# TokTok_Bluetooth.net
KiCad netlist of a schematic drawn in EAGLE
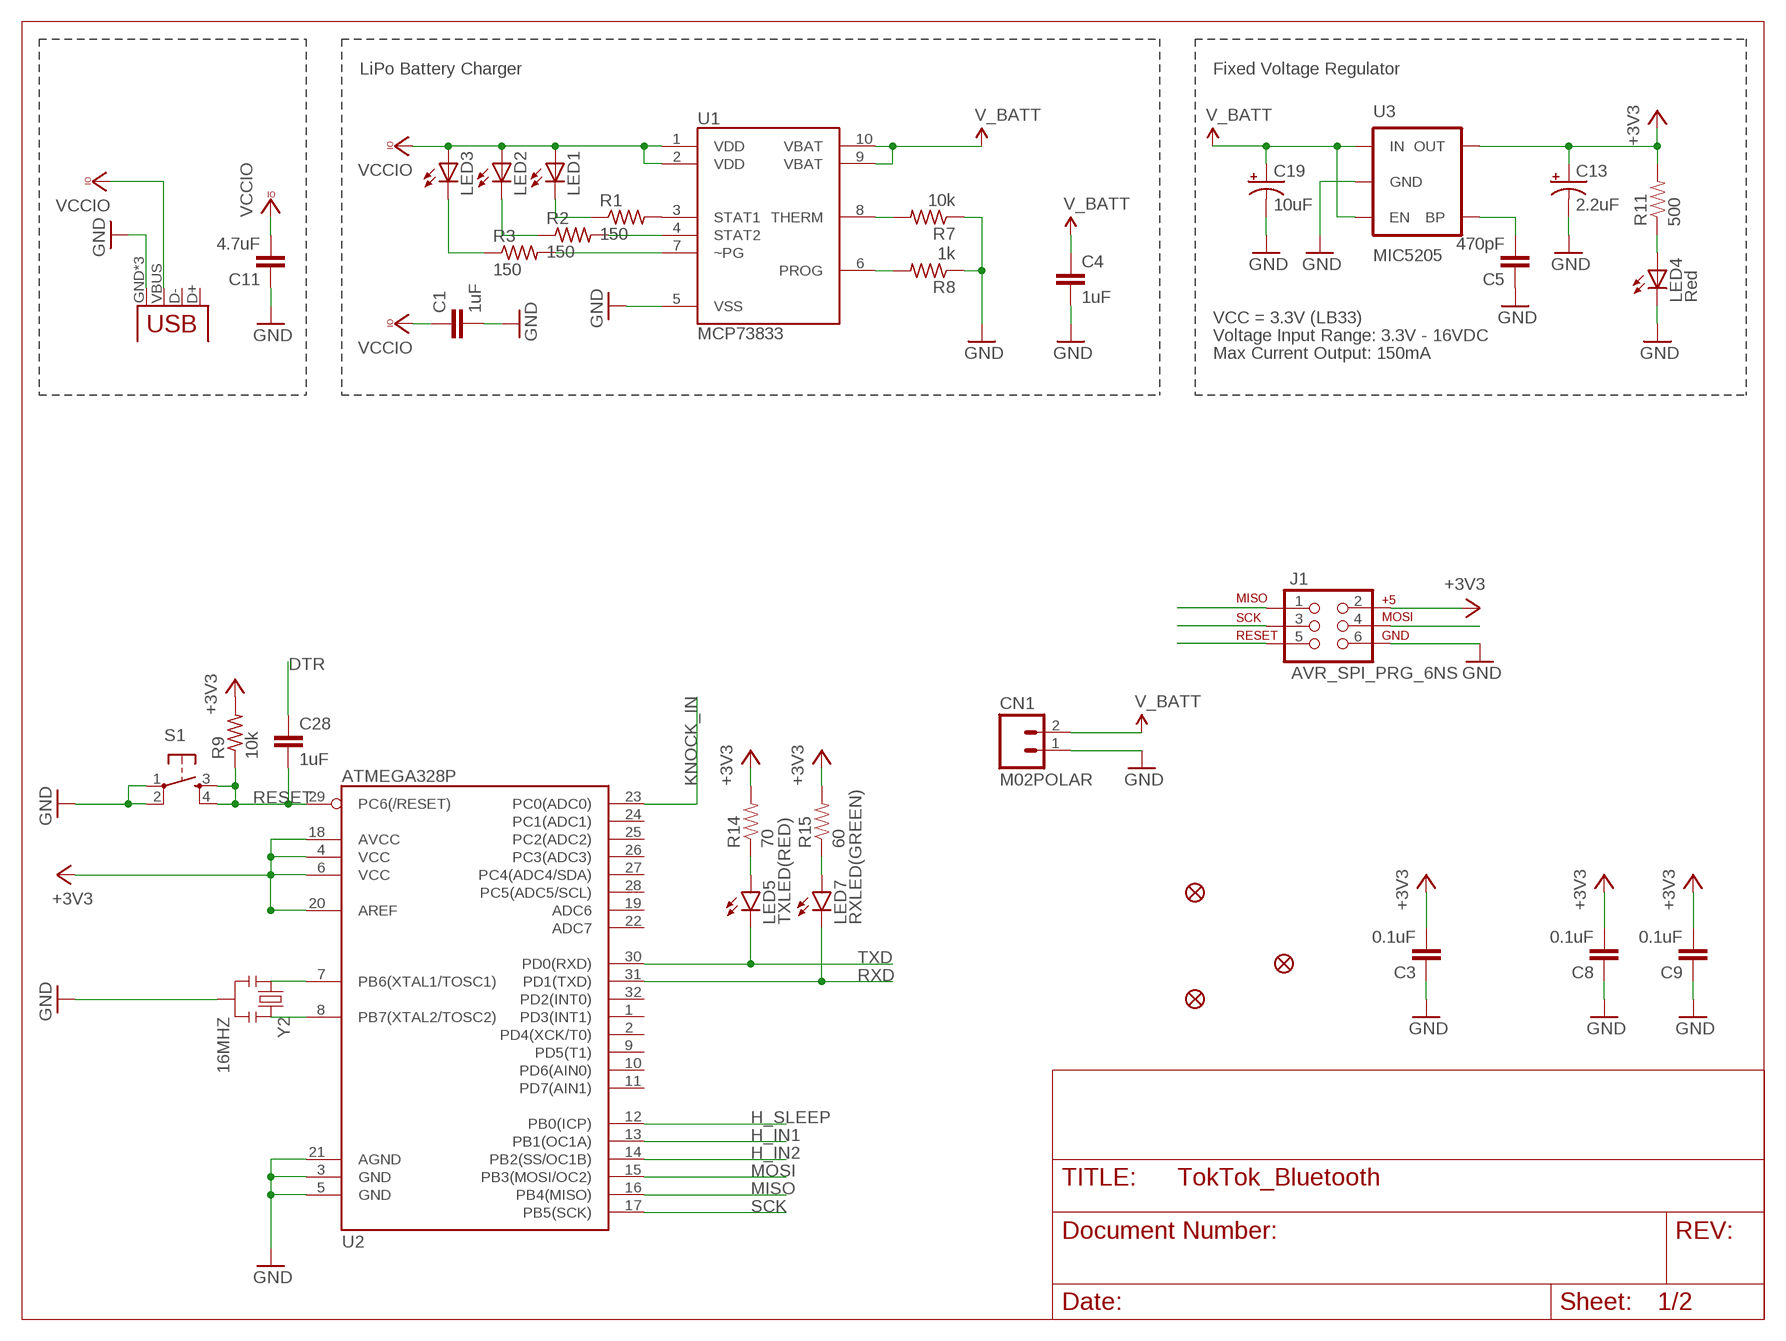
[diagram p0: schematic, sheet 1, part 1 of 2]
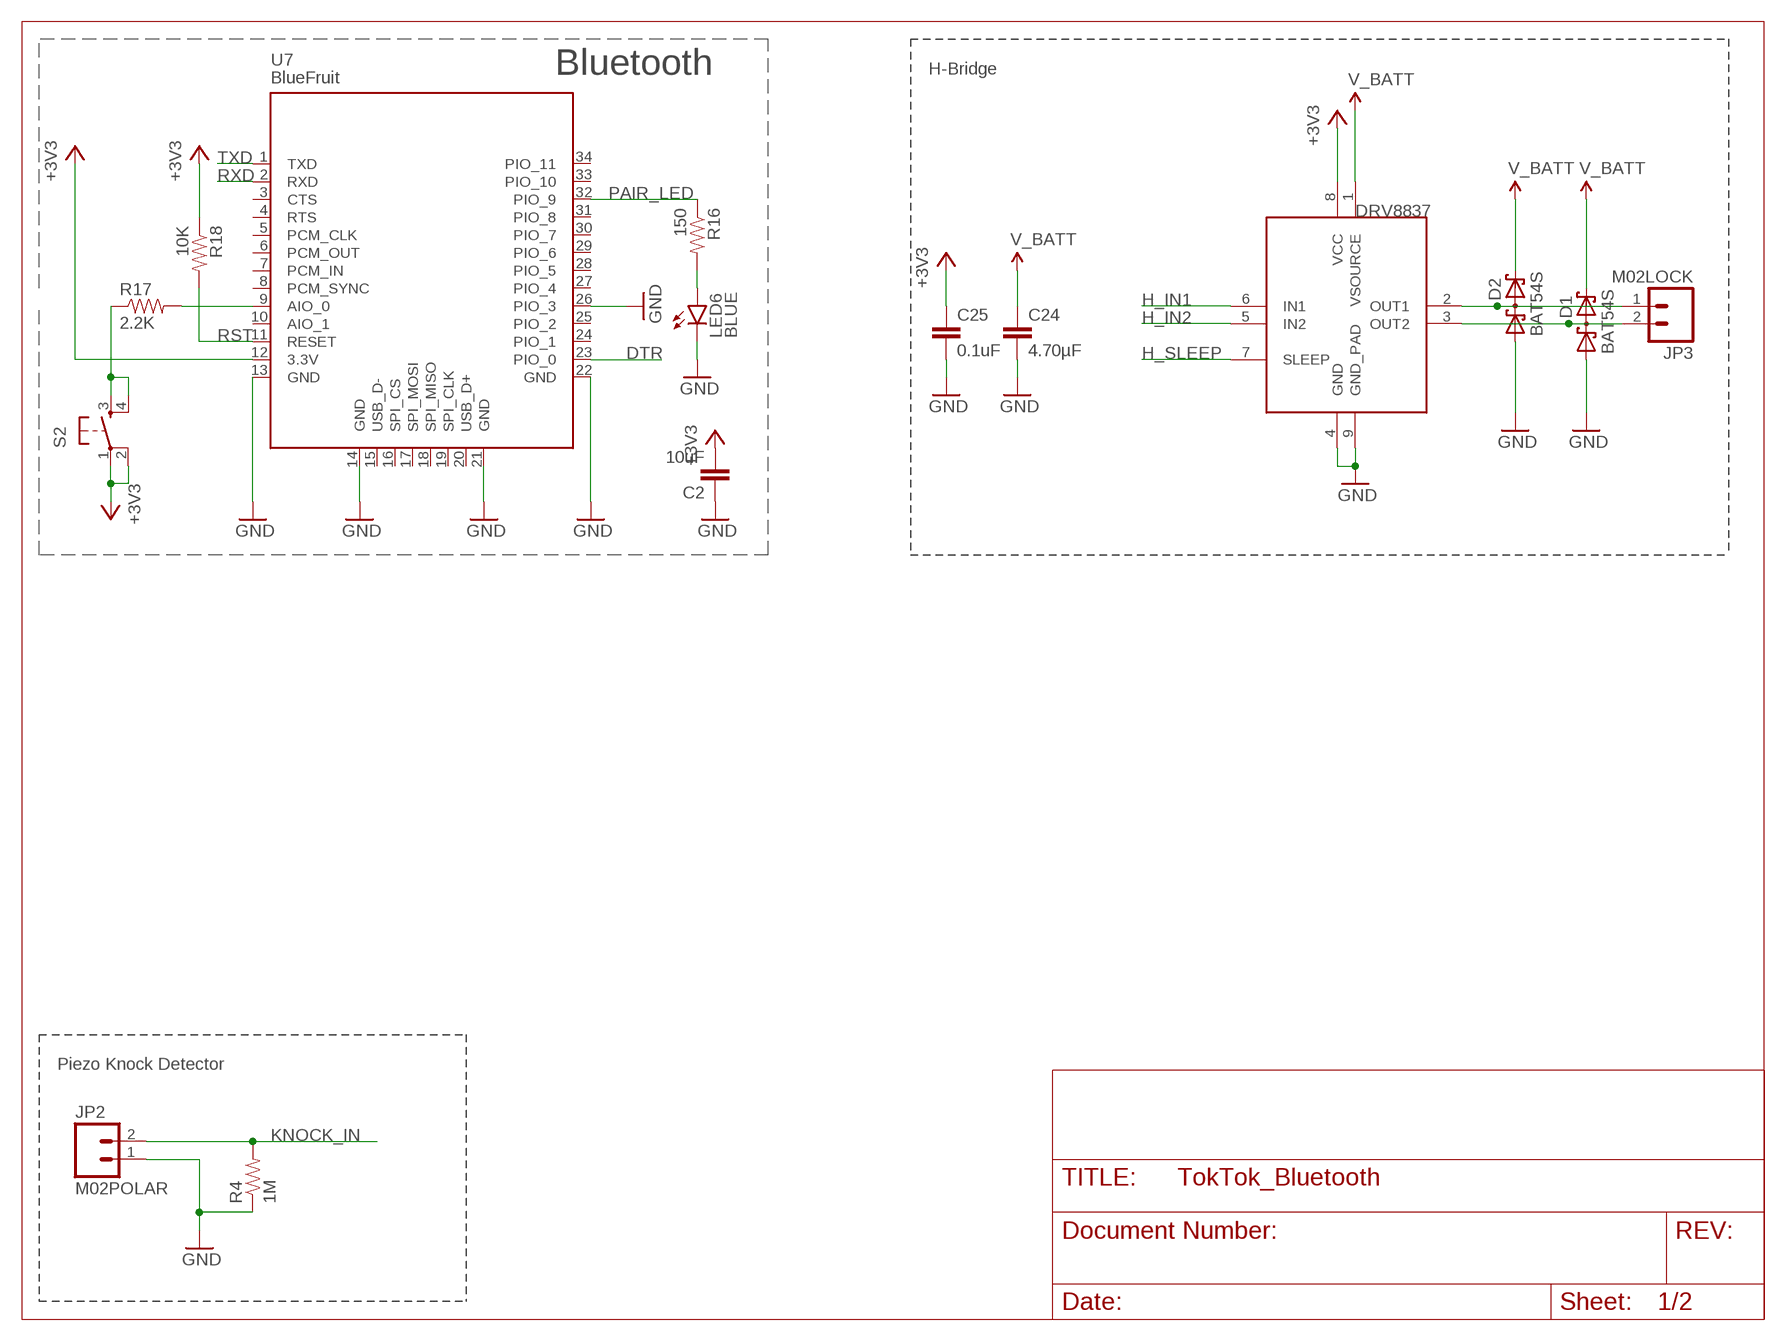
[diagram p1: schematic, sheet 1, part 2 of 2]

(export (version "E")
  (design (tool "Eeschema 10.0.6"))
  (components
    (comp (ref "C1")
      (value "1uF")
      (footprint "eagle-import:C0805K")
      (libsource (lib "eagle-import") (part "C-EUC0805K"))
    )
    (comp (ref "C2")
      (value "10uF")
      (footprint "eagle-import:0805")
      (libsource (lib "eagle-import") (part "CAP0805"))
    )
    (comp (ref "C3")
      (value "0.1uF")
      (footprint "eagle-import:C0805K")
      (libsource (lib "eagle-import") (part "C-EUC0805K"))
    )
    (comp (ref "C4")
      (value "1uF")
      (footprint "eagle-import:C0805K")
      (libsource (lib "eagle-import") (part "C-EUC0805K"))
    )
    (comp (ref "C5")
      (value "470pF")
      (footprint "eagle-import:0805")
      (libsource (lib "eagle-import") (part "CAP0805"))
    )
    (comp (ref "C8")
      (value "0.1uF")
      (footprint "eagle-import:C0805K")
      (libsource (lib "eagle-import") (part "C-EUC0805K"))
    )
    (comp (ref "C9")
      (value "0.1uF")
      (footprint "eagle-import:C0805K")
      (libsource (lib "eagle-import") (part "C-EUC0805K"))
    )
    (comp (ref "C11")
      (value "4.7uF")
      (footprint "eagle-import:C0805K")
      (libsource (lib "eagle-import") (part "C-EUC0805K"))
    )
    (comp (ref "C13")
      (value "2.2uF")
      (footprint "eagle-import:EIA3216")
      (libsource (lib "eagle-import") (part "CAP_POL1206"))
    )
    (comp (ref "C19")
      (value "10uF")
      (footprint "eagle-import:EIA3216")
      (libsource (lib "eagle-import") (part "CAP_POL1206"))
    )
    (comp (ref "C24")
      (value "4.70µF")
      (footprint "eagle-import:0805")
      (libsource (lib "eagle-import") (part "CAP0805"))
    )
    (comp (ref "C25")
      (value "0.1uF")
      (footprint "eagle-import:0805")
      (libsource (lib "eagle-import") (part "CAP0805"))
    )
    (comp (ref "C28")
      (value "1uF")
      (footprint "eagle-import:0805")
      (libsource (lib "eagle-import") (part "CAP0805"))
    )
    (comp (ref "CN1")
      (value "M02POLAR")
      (footprint "eagle-import:MOLEX-1X2")
      (libsource (lib "eagle-import") (part "M02POLAR"))
    )
    (comp (ref "D1")
      (value "BAT54S")
      (footprint "eagle-import:SOT23")
      (libsource (lib "eagle-import") (part "BAT54S"))
    )
    (comp (ref "D2")
      (value "BAT54S")
      (footprint "eagle-import:SOT23")
      (libsource (lib "eagle-import") (part "BAT54S"))
    )
    (comp (ref "FID1")
      (value "FIDUCIAL\"\"")
      (footprint "eagle-import:FIDUCIAL_1MM")
      (libsource (lib "eagle-import") (part "FIDUCIAL{dblquote}{dblquote}"))
    )
    (comp (ref "FID2")
      (value "FIDUCIAL\"\"")
      (footprint "eagle-import:FIDUCIAL_1MM")
      (libsource (lib "eagle-import") (part "FIDUCIAL{dblquote}{dblquote}"))
    )
    (comp (ref "FID3")
      (value "FIDUCIAL\"\"")
      (footprint "eagle-import:FIDUCIAL_1MM")
      (libsource (lib "eagle-import") (part "FIDUCIAL{dblquote}{dblquote}"))
    )
    (comp (ref "IC2")
      (value "DRV8837")
      (footprint "eagle-import:WSON-8")
      (libsource (lib "eagle-import") (part "DRV8837"))
    )
    (comp (ref "J1")
      (value "AVR_SPI_PRG_6NS")
      (footprint "eagle-import:2X3-NS")
      (libsource (lib "eagle-import") (part "AVR_SPI_PRG_6NS"))
    )
    (comp (ref "JP1")
      (value "USB-MICROB")
      (footprint "eagle-import:USB-MICROB")
      (libsource (lib "eagle-import") (part "USB-MICROB"))
    )
    (comp (ref "JP2")
      (value "M02POLAR")
      (footprint "eagle-import:MOLEX-1X2")
      (libsource (lib "eagle-import") (part "M02POLAR"))
    )
    (comp (ref "JP3")
      (value "M02LOCK")
      (footprint "eagle-import:1X02_LOCK")
      (libsource (lib "eagle-import") (part "M02LOCK"))
    )
    (comp (ref "LED1")
      (value "LEDCHIPLED_1206")
      (footprint "eagle-import:CHIPLED_1206")
      (libsource (lib "eagle-import") (part "LEDCHIPLED_1206"))
    )
    (comp (ref "LED2")
      (value "LEDCHIPLED_1206")
      (footprint "eagle-import:CHIPLED_1206")
      (libsource (lib "eagle-import") (part "LEDCHIPLED_1206"))
    )
    (comp (ref "LED3")
      (value "LEDCHIPLED_1206")
      (footprint "eagle-import:CHIPLED_1206")
      (libsource (lib "eagle-import") (part "LEDCHIPLED_1206"))
    )
    (comp (ref "LED4")
      (value "Red")
      (footprint "eagle-import:LED-1206")
      (libsource (lib "eagle-import") (part "LED-RED1206"))
    )
    (comp (ref "LED5")
      (value "TXLED(RED)")
      (footprint "eagle-import:LED-1206")
      (libsource (lib "eagle-import") (part "LED1206"))
    )
    (comp (ref "LED6")
      (value "BLUE")
      (footprint "eagle-import:LED-1206")
      (libsource (lib "eagle-import") (part "LED1206"))
    )
    (comp (ref "LED7")
      (value "RXLED(GREEN)")
      (footprint "eagle-import:LED-1206")
      (libsource (lib "eagle-import") (part "LED1206"))
    )
    (comp (ref "R1")
      (value "150")
      (footprint "eagle-import:M0805")
      (libsource (lib "eagle-import") (part "R-US_M0805"))
    )
    (comp (ref "R2")
      (value "150")
      (footprint "eagle-import:M0805")
      (libsource (lib "eagle-import") (part "R-US_M0805"))
    )
    (comp (ref "R3")
      (value "150")
      (footprint "eagle-import:M0805")
      (libsource (lib "eagle-import") (part "R-US_M0805"))
    )
    (comp (ref "R4")
      (value "1M")
      (footprint "eagle-import:0805")
      (libsource (lib "eagle-import") (part "RESISTOR0805-RES"))
    )
    (comp (ref "R7")
      (value "10k")
      (footprint "eagle-import:M0805")
      (libsource (lib "eagle-import") (part "R-US_M0805"))
    )
    (comp (ref "R8")
      (value "1k")
      (footprint "eagle-import:M0805")
      (libsource (lib "eagle-import") (part "R-US_M0805"))
    )
    (comp (ref "R9")
      (value "10k")
      (footprint "eagle-import:M0805")
      (libsource (lib "eagle-import") (part "R-US_M0805"))
    )
    (comp (ref "R11")
      (value "500")
      (footprint "eagle-import:0805")
      (libsource (lib "eagle-import") (part "RESISTOR0805-RES"))
    )
    (comp (ref "R14")
      (value "70")
      (footprint "eagle-import:0805")
      (libsource (lib "eagle-import") (part "RESISTOR0805-RES"))
    )
    (comp (ref "R15")
      (value "60")
      (footprint "eagle-import:0805")
      (libsource (lib "eagle-import") (part "RESISTOR0805-RES"))
    )
    (comp (ref "R16")
      (value "150")
      (footprint "eagle-import:0805")
      (libsource (lib "eagle-import") (part "RESISTOR0805-RES"))
    )
    (comp (ref "R17")
      (value "2.2K")
      (footprint "eagle-import:0805")
      (libsource (lib "eagle-import") (part "RESISTOR0805-RES"))
    )
    (comp (ref "R18")
      (value "10K")
      (footprint "eagle-import:0805")
      (libsource (lib "eagle-import") (part "RESISTOR0805-RES"))
    )
    (comp (ref "S1")
      (value "TAC_SWITCHSMD")
      (footprint "eagle-import:TACTILE-SWITCH-SMD")
      (libsource (lib "eagle-import") (part "TAC_SWITCHSMD"))
    )
    (comp (ref "S2")
      (value "TAC_SWITCHSMD")
      (footprint "eagle-import:TACTILE-SWITCH-SMD")
      (libsource (lib "eagle-import") (part "TAC_SWITCHSMD"))
    )
    (comp (ref "U1")
      (value "MCP73833")
      (footprint "eagle-import:MSOP-10")
      (libsource (lib "eagle-import") (part "MCP73833"))
    )
    (comp (ref "U2")
      (value "ATMEGA328P")
      (footprint "eagle-import:TQFP32-08")
      (libsource (lib "eagle-import") (part "ATMEGA328_SMT"))
    )
    (comp (ref "U3")
      (value "MIC5205")
      (footprint "eagle-import:SOT23-5")
      (libsource (lib "eagle-import") (part "V_REG_LDOSMD"))
    )
    (comp (ref "U7")
      (value "BlueFruit")
      (footprint "eagle-import:BLUETOOTH_MODULE")
      (libsource (lib "eagle-import") (part "BLUETOOTH_MODULE"))
    )
    (comp (ref "Y2")
      (value "16MHZ")
      (footprint "eagle-import:RESONATOR-SMD")
      (libsource (lib "eagle-import") (part "RESONATOR8MHZ"))
    )
  )
  (nets
    (net (code "1") (name "+3V3") (class "Default")
      (node (ref "C13") (pin "A") (pinfunction "+_A") (pintype "passive"))
      (node (ref "C2") (pin "2") (pinfunction "2_2") (pintype "passive"))
      (node (ref "C25") (pin "1") (pinfunction "1_1") (pintype "passive"))
      (node (ref "C3") (pin "2") (pinfunction "2_2") (pintype "passive"))
      (node (ref "C8") (pin "2") (pinfunction "2_2") (pintype "passive"))
      (node (ref "C9") (pin "2") (pinfunction "2_2") (pintype "passive"))
      (node (ref "IC2") (pin "8") (pinfunction "VCC_8") (pintype "bidirectional"))
      (node (ref "J1") (pin "2") (pinfunction "2_2") (pintype "passive"))
      (node (ref "R11") (pin "2") (pinfunction "2_2") (pintype "passive"))
      (node (ref "R14") (pin "2") (pinfunction "2_2") (pintype "passive"))
      (node (ref "R15") (pin "2") (pinfunction "2_2") (pintype "passive"))
      (node (ref "R18") (pin "1") (pinfunction "1_1") (pintype "passive"))
      (node (ref "R9") (pin "2") (pinfunction "2_2") (pintype "passive"))
      (node (ref "S2") (pin "1") (pinfunction "1_1") (pintype "passive"))
      (node (ref "S2") (pin "2") (pinfunction "2_2") (pintype "passive"))
      (node (ref "U2") (pin "18") (pinfunction "AVCC_18") (pintype "bidirectional"))
      (node (ref "U2") (pin "20") (pinfunction "AREF_20") (pintype "bidirectional"))
      (node (ref "U2") (pin "4") (pinfunction "VCC_4") (pintype "bidirectional"))
      (node (ref "U2") (pin "6") (pinfunction "VCC_6") (pintype "bidirectional"))
      (node (ref "U3") (pin "5") (pinfunction "OUT_5") (pintype "passive"))
      (node (ref "U7") (pin "12") (pinfunction "3.3V_12") (pintype "power_in"))
    )
    (net (code "2") (name "DTR") (class "Default")
      (node (ref "C28") (pin "1") (pinfunction "1_1") (pintype "passive"))
      (node (ref "U7") (pin "23") (pinfunction "PIO_0_23") (pintype "bidirectional"))
    )
    (net (code "3") (name "GND") (class "Default")
      (node (ref "C1") (pin "2") (pinfunction "2_2") (pintype "passive"))
      (node (ref "C11") (pin "1") (pinfunction "1_1") (pintype "passive"))
      (node (ref "C13") (pin "C") (pinfunction "-_C") (pintype "passive"))
      (node (ref "C19") (pin "C") (pinfunction "-_C") (pintype "passive"))
      (node (ref "C2") (pin "1") (pinfunction "1_1") (pintype "passive"))
      (node (ref "C24") (pin "2") (pinfunction "2_2") (pintype "passive"))
      (node (ref "C25") (pin "2") (pinfunction "2_2") (pintype "passive"))
      (node (ref "C3") (pin "1") (pinfunction "1_1") (pintype "passive"))
      (node (ref "C4") (pin "2") (pinfunction "2_2") (pintype "passive"))
      (node (ref "C5") (pin "1") (pinfunction "1_1") (pintype "passive"))
      (node (ref "C8") (pin "1") (pinfunction "1_1") (pintype "passive"))
      (node (ref "C9") (pin "1") (pinfunction "1_1") (pintype "passive"))
      (node (ref "CN1") (pin "1") (pinfunction "1_1") (pintype "passive"))
      (node (ref "D1") (pin "1") (pinfunction "A1_1") (pintype "passive"))
      (node (ref "D2") (pin "1") (pinfunction "A1_1") (pintype "passive"))
      (node (ref "IC2") (pin "4") (pinfunction "GND_4") (pintype "bidirectional"))
      (node (ref "IC2") (pin "9") (pinfunction "GND_PAD_9") (pintype "bidirectional"))
      (node (ref "J1") (pin "6") (pinfunction "6_6") (pintype "passive"))
      (node (ref "JP1") (pin "GND") (pinfunction "GND_GND") (pintype "bidirectional"))
      (node (ref "JP1") (pin "MT1") (pinfunction "GND_MT1") (pintype "bidirectional"))
      (node (ref "JP1") (pin "MT2") (pinfunction "GND_MT2") (pintype "bidirectional"))
      (node (ref "JP2") (pin "1") (pinfunction "1_1") (pintype "passive"))
      (node (ref "LED4") (pin "C") (pinfunction "C_C") (pintype "passive"))
      (node (ref "LED6") (pin "C") (pinfunction "C_C") (pintype "passive"))
      (node (ref "R4") (pin "1") (pinfunction "1_1") (pintype "passive"))
      (node (ref "R7") (pin "1") (pinfunction "1_1") (pintype "passive"))
      (node (ref "R8") (pin "1") (pinfunction "1_1") (pintype "passive"))
      (node (ref "S1") (pin "1") (pinfunction "1_1") (pintype "passive"))
      (node (ref "S1") (pin "2") (pinfunction "2_2") (pintype "passive"))
      (node (ref "U1") (pin "5") (pinfunction "VSS_5") (pintype "bidirectional"))
      (node (ref "U2") (pin "21") (pinfunction "AGND_21") (pintype "bidirectional"))
      (node (ref "U2") (pin "3") (pinfunction "GND_3") (pintype "bidirectional"))
      (node (ref "U2") (pin "5") (pinfunction "GND_5") (pintype "bidirectional"))
      (node (ref "U3") (pin "2") (pinfunction "GND_2") (pintype "input"))
      (node (ref "U7") (pin "13") (pinfunction "GND_13") (pintype "power_in"))
      (node (ref "U7") (pin "14") (pinfunction "GND_14") (pintype "power_in"))
      (node (ref "U7") (pin "21") (pinfunction "GND_21") (pintype "power_in"))
      (node (ref "U7") (pin "22") (pinfunction "GND_22") (pintype "power_in"))
      (node (ref "U7") (pin "26") (pinfunction "PIO_3_26") (pintype "bidirectional"))
      (node (ref "Y2") (pin "2") (pinfunction "2_2") (pintype "passive"))
    )
    (net (code "4") (name "H_IN1") (class "Default")
      (node (ref "IC2") (pin "6") (pinfunction "IN1_6") (pintype "bidirectional"))
      (node (ref "U2") (pin "13") (pinfunction "PB1(OC1A)_13") (pintype "bidirectional"))
    )
    (net (code "5") (name "H_IN2") (class "Default")
      (node (ref "IC2") (pin "5") (pinfunction "IN2_5") (pintype "bidirectional"))
      (node (ref "U2") (pin "14") (pinfunction "PB2(SS/OC1B)_14") (pintype "bidirectional"))
    )
    (net (code "6") (name "H_SLEEP") (class "Default")
      (node (ref "IC2") (pin "7") (pinfunction "SLEEP_7") (pintype "bidirectional"))
      (node (ref "U2") (pin "12") (pinfunction "PB0(ICP)_12") (pintype "bidirectional"))
    )
    (net (code "7") (name "KNOCK_IN") (class "Default")
      (node (ref "JP2") (pin "2") (pinfunction "2_2") (pintype "passive"))
      (node (ref "R4") (pin "2") (pinfunction "2_2") (pintype "passive"))
      (node (ref "U2") (pin "23") (pinfunction "PC0(ADC0)_23") (pintype "bidirectional"))
    )
    (net (code "8") (name "MISO") (class "Default")
      (node (ref "J1") (pin "1") (pinfunction "1_1") (pintype "passive"))
      (node (ref "U2") (pin "16") (pinfunction "PB4(MISO)_16") (pintype "bidirectional"))
    )
    (net (code "9") (name "MOSI") (class "Default")
      (node (ref "J1") (pin "4") (pinfunction "4_4") (pintype "passive"))
      (node (ref "U2") (pin "15") (pinfunction "PB3(MOSI/OC2)_15") (pintype "bidirectional"))
    )
    (net (code "10") (name "Net-(D1-C1A2)") (class "Default")
      (node (ref "D1") (pin "3") (pinfunction "C1A2_3") (pintype "passive"))
      (node (ref "IC2") (pin "3") (pinfunction "OUT2_3") (pintype "bidirectional"))
      (node (ref "JP3") (pin "2") (pinfunction "2_2") (pintype "passive"))
    )
    (net (code "11") (name "Net-(D2-C1A2)") (class "Default")
      (node (ref "D2") (pin "3") (pinfunction "C1A2_3") (pintype "passive"))
      (node (ref "IC2") (pin "2") (pinfunction "OUT1_2") (pintype "bidirectional"))
      (node (ref "JP3") (pin "1") (pinfunction "1_1") (pintype "passive"))
    )
    (net (code "12") (name "Net-(LED1-PadC)") (class "Default")
      (node (ref "LED1") (pin "C") (pinfunction "C_C") (pintype "passive"))
      (node (ref "R1") (pin "1") (pinfunction "1_1") (pintype "passive"))
    )
    (net (code "13") (name "Net-(LED2-PadC)") (class "Default")
      (node (ref "LED2") (pin "C") (pinfunction "C_C") (pintype "passive"))
      (node (ref "R2") (pin "1") (pinfunction "1_1") (pintype "passive"))
    )
    (net (code "14") (name "Net-(LED3-PadC)") (class "Default")
      (node (ref "LED3") (pin "C") (pinfunction "C_C") (pintype "passive"))
      (node (ref "R3") (pin "1") (pinfunction "1_1") (pintype "passive"))
    )
    (net (code "15") (name "Net-(LED4-PadA)") (class "Default")
      (node (ref "LED4") (pin "A") (pinfunction "A_A") (pintype "passive"))
      (node (ref "R11") (pin "1") (pinfunction "1_1") (pintype "passive"))
    )
    (net (code "16") (name "Net-(LED5-PadA)") (class "Default")
      (node (ref "LED5") (pin "A") (pinfunction "A_A") (pintype "passive"))
      (node (ref "R14") (pin "1") (pinfunction "1_1") (pintype "passive"))
    )
    (net (code "17") (name "Net-(LED6-PadA)") (class "Default")
      (node (ref "LED6") (pin "A") (pinfunction "A_A") (pintype "passive"))
      (node (ref "R16") (pin "2") (pinfunction "2_2") (pintype "passive"))
    )
    (net (code "18") (name "Net-(LED7-PadA)") (class "Default")
      (node (ref "LED7") (pin "A") (pinfunction "A_A") (pintype "passive"))
      (node (ref "R15") (pin "1") (pinfunction "1_1") (pintype "passive"))
    )
    (net (code "19") (name "Net-(R17-Pad1)") (class "Default")
      (node (ref "R17") (pin "1") (pinfunction "1_1") (pintype "passive"))
      (node (ref "S2") (pin "3") (pinfunction "3_3") (pintype "passive"))
      (node (ref "S2") (pin "4") (pinfunction "4_4") (pintype "passive"))
    )
    (net (code "20") (name "Net-(U1-PROG)") (class "Default")
      (node (ref "R8") (pin "2") (pinfunction "2_2") (pintype "passive"))
      (node (ref "U1") (pin "6") (pinfunction "PROG_6") (pintype "bidirectional"))
    )
    (net (code "21") (name "Net-(U1-STAT1)") (class "Default")
      (node (ref "R1") (pin "2") (pinfunction "2_2") (pintype "passive"))
      (node (ref "U1") (pin "3") (pinfunction "STAT1_3") (pintype "bidirectional"))
    )
    (net (code "22") (name "Net-(U1-STAT2)") (class "Default")
      (node (ref "R2") (pin "2") (pinfunction "2_2") (pintype "passive"))
      (node (ref "U1") (pin "4") (pinfunction "STAT2_4") (pintype "bidirectional"))
    )
    (net (code "23") (name "Net-(U1-THERM)") (class "Default")
      (node (ref "R7") (pin "2") (pinfunction "2_2") (pintype "passive"))
      (node (ref "U1") (pin "8") (pinfunction "THERM_8") (pintype "bidirectional"))
    )
    (net (code "24") (name "Net-(U1-~{PG})") (class "Default")
      (node (ref "R3") (pin "2") (pinfunction "2_2") (pintype "passive"))
      (node (ref "U1") (pin "7") (pinfunction "~{PG}_7") (pintype "bidirectional"))
    )
    (net (code "25") (name "Net-(U2-PB6(XTAL1{slash}TOSC1))") (class "Default")
      (node (ref "U2") (pin "7") (pinfunction "PB6(XTAL1/TOSC1)_7") (pintype "bidirectional"))
      (node (ref "Y2") (pin "1") (pinfunction "1_1") (pintype "passive"))
    )
    (net (code "26") (name "Net-(U2-PB7(XTAL2{slash}TOSC2))") (class "Default")
      (node (ref "U2") (pin "8") (pinfunction "PB7(XTAL2/TOSC2)_8") (pintype "bidirectional"))
      (node (ref "Y2") (pin "3") (pinfunction "3_3") (pintype "passive"))
    )
    (net (code "27") (name "Net-(U3-BP)") (class "Default")
      (node (ref "C5") (pin "2") (pinfunction "2_2") (pintype "passive"))
      (node (ref "U3") (pin "4") (pinfunction "BP_4") (pintype "input"))
    )
    (net (code "28") (name "Net-(U7-AIO_0)") (class "Default")
      (node (ref "R17") (pin "2") (pinfunction "2_2") (pintype "passive"))
      (node (ref "U7") (pin "9") (pinfunction "AIO_0_9") (pintype "bidirectional"))
    )
    (net (code "29") (name "PAIR_LED") (class "Default")
      (node (ref "R16") (pin "1") (pinfunction "1_1") (pintype "passive"))
      (node (ref "U7") (pin "32") (pinfunction "PIO_9_32") (pintype "bidirectional"))
    )
    (net (code "30") (name "RESET") (class "Default")
      (node (ref "C28") (pin "2") (pinfunction "2_2") (pintype "passive"))
      (node (ref "J1") (pin "5") (pinfunction "5_5") (pintype "passive"))
      (node (ref "R9") (pin "1") (pinfunction "1_1") (pintype "passive"))
      (node (ref "S1") (pin "3") (pinfunction "3_3") (pintype "passive"))
      (node (ref "S1") (pin "4") (pinfunction "4_4") (pintype "passive"))
      (node (ref "U2") (pin "29") (pinfunction "PC6(/RESET)_29") (pintype "bidirectional"))
    )
    (net (code "31") (name "RST") (class "Default")
      (node (ref "R18") (pin "2") (pinfunction "2_2") (pintype "passive"))
      (node (ref "U7") (pin "11") (pinfunction "RESET_11") (pintype "bidirectional"))
    )
    (net (code "32") (name "RXD") (class "Default")
      (node (ref "LED7") (pin "C") (pinfunction "C_C") (pintype "passive"))
      (node (ref "U2") (pin "31") (pinfunction "PD1(TXD)_31") (pintype "bidirectional"))
      (node (ref "U7") (pin "2") (pinfunction "RXD_2") (pintype "bidirectional"))
    )
    (net (code "33") (name "SCK") (class "Default")
      (node (ref "J1") (pin "3") (pinfunction "3_3") (pintype "passive"))
      (node (ref "U2") (pin "17") (pinfunction "PB5(SCK)_17") (pintype "bidirectional"))
    )
    (net (code "34") (name "TXD") (class "Default")
      (node (ref "LED5") (pin "C") (pinfunction "C_C") (pintype "passive"))
      (node (ref "U2") (pin "30") (pinfunction "PD0(RXD)_30") (pintype "bidirectional"))
      (node (ref "U7") (pin "1") (pinfunction "TXD_1") (pintype "bidirectional"))
    )
    (net (code "35") (name "VCCIO") (class "Default")
      (node (ref "C1") (pin "1") (pinfunction "1_1") (pintype "passive"))
      (node (ref "C11") (pin "2") (pinfunction "2_2") (pintype "passive"))
      (node (ref "JP1") (pin "VBUS") (pinfunction "VBUS_VBUS") (pintype "bidirectional"))
      (node (ref "LED1") (pin "A") (pinfunction "A_A") (pintype "passive"))
      (node (ref "LED2") (pin "A") (pinfunction "A_A") (pintype "passive"))
      (node (ref "LED3") (pin "A") (pinfunction "A_A") (pintype "passive"))
      (node (ref "U1") (pin "1") (pinfunction "VDD_1") (pintype "bidirectional"))
      (node (ref "U1") (pin "2") (pinfunction "VDD_2") (pintype "bidirectional"))
    )
    (net (code "36") (name "V_BATT") (class "Default")
      (node (ref "C19") (pin "A") (pinfunction "+_A") (pintype "passive"))
      (node (ref "C24") (pin "1") (pinfunction "1_1") (pintype "passive"))
      (node (ref "C4") (pin "1") (pinfunction "1_1") (pintype "passive"))
      (node (ref "CN1") (pin "2") (pinfunction "2_2") (pintype "passive"))
      (node (ref "D1") (pin "2") (pinfunction "C2_2") (pintype "passive"))
      (node (ref "D2") (pin "2") (pinfunction "C2_2") (pintype "passive"))
      (node (ref "IC2") (pin "1") (pinfunction "VSOURCE_1") (pintype "bidirectional"))
      (node (ref "U1") (pin "10") (pinfunction "VBAT_10") (pintype "bidirectional"))
      (node (ref "U1") (pin "9") (pinfunction "VBAT_9") (pintype "bidirectional"))
      (node (ref "U3") (pin "1") (pinfunction "IN_1") (pintype "input"))
      (node (ref "U3") (pin "3") (pinfunction "EN_3") (pintype "input"))
    )
    (net (code "37") (name "unconnected-(JP1-PadD+)") (class "Default")
      (node (ref "JP1") (pin "D+") (pinfunction "D+_D+") (pintype "bidirectional"))
    )
    (net (code "38") (name "unconnected-(JP1-PadD-)") (class "Default")
      (node (ref "JP1") (pin "D-") (pinfunction "D-_D-") (pintype "bidirectional"))
    )
    (net (code "39") (name "unconnected-(U2-ADC6-Pad19)") (class "Default")
      (node (ref "U2") (pin "19") (pinfunction "ADC6_19") (pintype "bidirectional"))
    )
    (net (code "40") (name "unconnected-(U2-ADC7-Pad22)") (class "Default")
      (node (ref "U2") (pin "22") (pinfunction "ADC7_22") (pintype "bidirectional"))
    )
    (net (code "41") (name "unconnected-(U2-PC1(ADC1)-Pad24)") (class "Default")
      (node (ref "U2") (pin "24") (pinfunction "PC1(ADC1)_24") (pintype "bidirectional"))
    )
    (net (code "42") (name "unconnected-(U2-PC2(ADC2)-Pad25)") (class "Default")
      (node (ref "U2") (pin "25") (pinfunction "PC2(ADC2)_25") (pintype "bidirectional"))
    )
    (net (code "43") (name "unconnected-(U2-PC3(ADC3)-Pad26)") (class "Default")
      (node (ref "U2") (pin "26") (pinfunction "PC3(ADC3)_26") (pintype "bidirectional"))
    )
    (net (code "44") (name "unconnected-(U2-PC4(ADC4{slash}SDA)-Pad27)") (class "Default")
      (node (ref "U2") (pin "27") (pinfunction "PC4(ADC4/SDA)_27") (pintype "bidirectional"))
    )
    (net (code "45") (name "unconnected-(U2-PC5(ADC5{slash}SCL)-Pad28)") (class "Default")
      (node (ref "U2") (pin "28") (pinfunction "PC5(ADC5/SCL)_28") (pintype "bidirectional"))
    )
    (net (code "46") (name "unconnected-(U2-PD2(INT0)-Pad32)") (class "Default")
      (node (ref "U2") (pin "32") (pinfunction "PD2(INT0)_32") (pintype "bidirectional"))
    )
    (net (code "47") (name "unconnected-(U2-PD3(INT1)-Pad1)") (class "Default")
      (node (ref "U2") (pin "1") (pinfunction "PD3(INT1)_1") (pintype "bidirectional"))
    )
    (net (code "48") (name "unconnected-(U2-PD4(XCK{slash}T0)-Pad2)") (class "Default")
      (node (ref "U2") (pin "2") (pinfunction "PD4(XCK/T0)_2") (pintype "bidirectional"))
    )
    (net (code "49") (name "unconnected-(U2-PD5(T1)-Pad9)") (class "Default")
      (node (ref "U2") (pin "9") (pinfunction "PD5(T1)_9") (pintype "bidirectional"))
    )
    (net (code "50") (name "unconnected-(U2-PD6(AIN0)-Pad10)") (class "Default")
      (node (ref "U2") (pin "10") (pinfunction "PD6(AIN0)_10") (pintype "bidirectional"))
    )
    (net (code "51") (name "unconnected-(U2-PD7(AIN1)-Pad11)") (class "Default")
      (node (ref "U2") (pin "11") (pinfunction "PD7(AIN1)_11") (pintype "bidirectional"))
    )
    (net (code "52") (name "unconnected-(U7-AIO_1-Pad10)") (class "Default")
      (node (ref "U7") (pin "10") (pinfunction "AIO_1_10") (pintype "bidirectional"))
    )
    (net (code "53") (name "unconnected-(U7-CTS-Pad3)") (class "Default")
      (node (ref "U7") (pin "3") (pinfunction "CTS_3") (pintype "bidirectional"))
    )
    (net (code "54") (name "unconnected-(U7-PCM_CLK-Pad5)") (class "Default")
      (node (ref "U7") (pin "5") (pinfunction "PCM_CLK_5") (pintype "bidirectional"))
    )
    (net (code "55") (name "unconnected-(U7-PCM_IN-Pad7)") (class "Default")
      (node (ref "U7") (pin "7") (pinfunction "PCM_IN_7") (pintype "bidirectional"))
    )
    (net (code "56") (name "unconnected-(U7-PCM_OUT-Pad6)") (class "Default")
      (node (ref "U7") (pin "6") (pinfunction "PCM_OUT_6") (pintype "bidirectional"))
    )
    (net (code "57") (name "unconnected-(U7-PCM_SYNC-Pad8)") (class "Default")
      (node (ref "U7") (pin "8") (pinfunction "PCM_SYNC_8") (pintype "bidirectional"))
    )
    (net (code "58") (name "unconnected-(U7-PIO_1-Pad24)") (class "Default")
      (node (ref "U7") (pin "24") (pinfunction "PIO_1_24") (pintype "bidirectional"))
    )
    (net (code "59") (name "unconnected-(U7-PIO_2-Pad25)") (class "Default")
      (node (ref "U7") (pin "25") (pinfunction "PIO_2_25") (pintype "bidirectional"))
    )
    (net (code "60") (name "unconnected-(U7-PIO_4-Pad27)") (class "Default")
      (node (ref "U7") (pin "27") (pinfunction "PIO_4_27") (pintype "bidirectional"))
    )
    (net (code "61") (name "unconnected-(U7-PIO_5-Pad28)") (class "Default")
      (node (ref "U7") (pin "28") (pinfunction "PIO_5_28") (pintype "bidirectional"))
    )
    (net (code "62") (name "unconnected-(U7-PIO_6-Pad29)") (class "Default")
      (node (ref "U7") (pin "29") (pinfunction "PIO_6_29") (pintype "bidirectional"))
    )
    (net (code "63") (name "unconnected-(U7-PIO_7-Pad30)") (class "Default")
      (node (ref "U7") (pin "30") (pinfunction "PIO_7_30") (pintype "bidirectional"))
    )
    (net (code "64") (name "unconnected-(U7-PIO_8-Pad31)") (class "Default")
      (node (ref "U7") (pin "31") (pinfunction "PIO_8_31") (pintype "bidirectional"))
    )
    (net (code "65") (name "unconnected-(U7-PIO_10-Pad33)") (class "Default")
      (node (ref "U7") (pin "33") (pinfunction "PIO_10_33") (pintype "bidirectional"))
    )
    (net (code "66") (name "unconnected-(U7-PIO_11-Pad34)") (class "Default")
      (node (ref "U7") (pin "34") (pinfunction "PIO_11_34") (pintype "bidirectional"))
    )
    (net (code "67") (name "unconnected-(U7-RTS-Pad4)") (class "Default")
      (node (ref "U7") (pin "4") (pinfunction "RTS_4") (pintype "bidirectional"))
    )
    (net (code "68") (name "unconnected-(U7-SPI_CLK-Pad19)") (class "Default")
      (node (ref "U7") (pin "19") (pinfunction "SPI_CLK_19") (pintype "bidirectional"))
    )
    (net (code "69") (name "unconnected-(U7-SPI_CS-Pad16)") (class "Default")
      (node (ref "U7") (pin "16") (pinfunction "SPI_CS_16") (pintype "bidirectional"))
    )
    (net (code "70") (name "unconnected-(U7-SPI_MISO-Pad18)") (class "Default")
      (node (ref "U7") (pin "18") (pinfunction "SPI_MISO_18") (pintype "bidirectional"))
    )
    (net (code "71") (name "unconnected-(U7-SPI_MOSI-Pad17)") (class "Default")
      (node (ref "U7") (pin "17") (pinfunction "SPI_MOSI_17") (pintype "bidirectional"))
    )
    (net (code "72") (name "unconnected-(U7-USB_D+-Pad20)") (class "Default")
      (node (ref "U7") (pin "20") (pinfunction "USB_D+_20") (pintype "bidirectional"))
    )
    (net (code "73") (name "unconnected-(U7-USB_D--Pad15)") (class "Default")
      (node (ref "U7") (pin "15") (pinfunction "USB_D-_15") (pintype "bidirectional"))
    )
  )
)
